# LED_PIPE_PROJECT.net
KiCad netlist of a schematic drawn in EAGLE
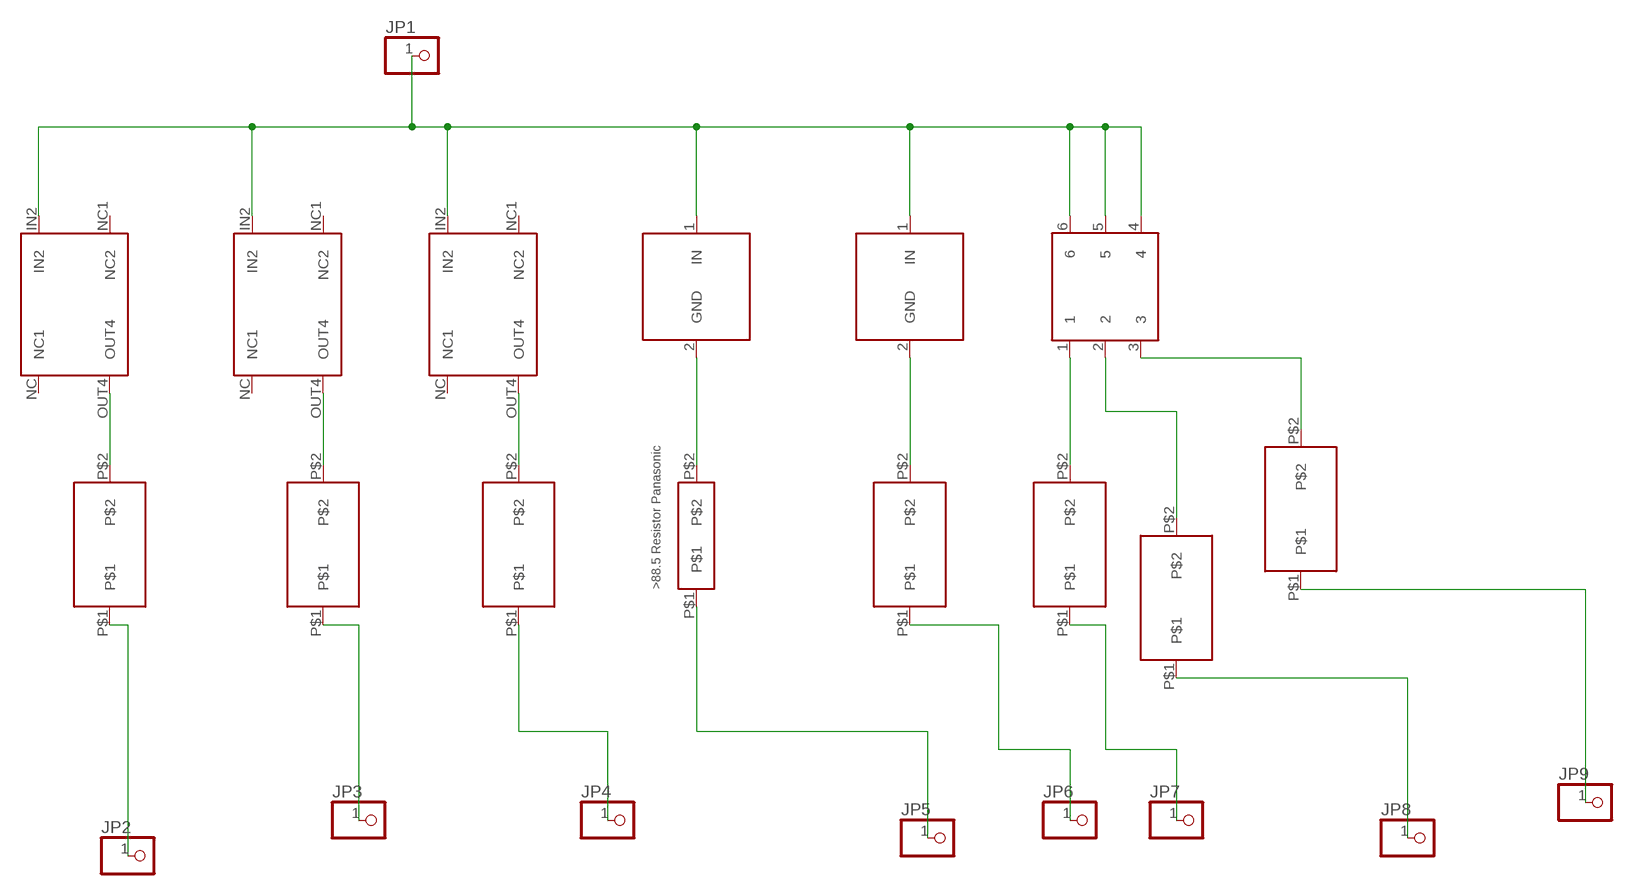
[diagram p0: schematic, sheet 1]

(export (version "E")
  (design (tool "Eeschema 10.0.6"))
  (components
    (comp (ref "JP1")
      (value "PINHD-1X1")
      (footprint "eagle-import:1X01")
      (libsource (lib "eagle-import") (part "PINHD-1X1"))
    )
    (comp (ref "JP2")
      (value "PINHD-1X1")
      (footprint "eagle-import:1X01")
      (libsource (lib "eagle-import") (part "PINHD-1X1"))
    )
    (comp (ref "JP3")
      (value "PINHD-1X1")
      (footprint "eagle-import:1X01")
      (libsource (lib "eagle-import") (part "PINHD-1X1"))
    )
    (comp (ref "JP4")
      (value "PINHD-1X1")
      (footprint "eagle-import:1X01")
      (libsource (lib "eagle-import") (part "PINHD-1X1"))
    )
    (comp (ref "JP5")
      (value "PINHD-1X1")
      (footprint "eagle-import:1X01")
      (libsource (lib "eagle-import") (part "PINHD-1X1"))
    )
    (comp (ref "JP6")
      (value "PINHD-1X1")
      (footprint "eagle-import:1X01")
      (libsource (lib "eagle-import") (part "PINHD-1X1"))
    )
    (comp (ref "JP7")
      (value "PINHD-1X1")
      (footprint "eagle-import:1X01")
      (libsource (lib "eagle-import") (part "PINHD-1X1"))
    )
    (comp (ref "JP8")
      (value "PINHD-1X1")
      (footprint "eagle-import:1X01")
      (libsource (lib "eagle-import") (part "PINHD-1X1"))
    )
    (comp (ref "JP9")
      (value "PINHD-1X1")
      (footprint "eagle-import:1X01")
      (libsource (lib "eagle-import") (part "PINHD-1X1"))
    )
    (comp (ref "U$1")
      (value "UV_LED")
      (footprint "eagle-import:UV_LED")
      (libsource (lib "eagle-import") (part "UV_LED"))
    )
    (comp (ref "U$2")
      (value "IR_LED")
      (footprint "eagle-import:IR_LED")
      (libsource (lib "eagle-import") (part "IR_LED"))
    )
    (comp (ref "U$3")
      (value "SMALL_RGB")
      (footprint "eagle-import:SMALL_RGB")
      (libsource (lib "eagle-import") (part "SMALL_RGB"))
    )
    (comp (ref "U$4")
      (value "SMALL_BRIGHT_COOL_WHITE")
      (footprint "eagle-import:SMALL_BRIGHT_COOL_WHITE")
      (libsource (lib "eagle-import") (part "SMALL_BRIGHT_COOL_WHITE"))
    )
    (comp (ref "U$5")
      (value "SMALL_BRIGHT_COOL_WHITE")
      (footprint "eagle-import:SMALL_BRIGHT_COOL_WHITE")
      (libsource (lib "eagle-import") (part "SMALL_BRIGHT_COOL_WHITE"))
    )
    (comp (ref "U$6")
      (value "SMALL_BRIGHT_COOL_WHITE")
      (footprint "eagle-import:SMALL_BRIGHT_COOL_WHITE")
      (libsource (lib "eagle-import") (part "SMALL_BRIGHT_COOL_WHITE"))
    )
    (comp (ref "U$7")
      (value "68_60_56_RESISTOR_VISHAY")
      (footprint "eagle-import:68_60_56_RESISTOR_VISHAY")
      (libsource (lib "eagle-import") (part "68_60_56_RESISTOR_VISHAY"))
    )
    (comp (ref "U$8")
      (value "68_60_56_RESISTOR_VISHAY")
      (footprint "eagle-import:68_60_56_RESISTOR_VISHAY")
      (libsource (lib "eagle-import") (part "68_60_56_RESISTOR_VISHAY"))
    )
    (comp (ref "U$9")
      (value "68_60_56_RESISTOR_VISHAY")
      (footprint "eagle-import:68_60_56_RESISTOR_VISHAY")
      (libsource (lib "eagle-import") (part "68_60_56_RESISTOR_VISHAY"))
    )
    (comp (ref "U$10")
      (value "88.5_RESISTOR_PANASONIC")
      (footprint "eagle-import:88.7_RESISTOR_PANASONIC")
      (libsource (lib "eagle-import") (part "88.5_RESISTOR_PANASONIC"))
    )
    (comp (ref "U$11")
      (value "68_60_56_RESISTOR_VISHAY")
      (footprint "eagle-import:68_60_56_RESISTOR_VISHAY")
      (libsource (lib "eagle-import") (part "68_60_56_RESISTOR_VISHAY"))
    )
    (comp (ref "U$12")
      (value "68_60_56_RESISTOR_VISHAY")
      (footprint "eagle-import:68_60_56_RESISTOR_VISHAY")
      (libsource (lib "eagle-import") (part "68_60_56_RESISTOR_VISHAY"))
    )
    (comp (ref "U$13")
      (value "68_60_56_RESISTOR_VISHAY")
      (footprint "eagle-import:68_60_56_RESISTOR_VISHAY")
      (libsource (lib "eagle-import") (part "68_60_56_RESISTOR_VISHAY"))
    )
    (comp (ref "U$14")
      (value "68_60_56_RESISTOR_VISHAY")
      (footprint "eagle-import:68_60_56_RESISTOR_VISHAY")
      (libsource (lib "eagle-import") (part "68_60_56_RESISTOR_VISHAY"))
    )
  )
  (nets
    (net (code "1") (name "Net-(JP2-Pad1)") (class "Default")
      (node (ref "JP2") (pin "1") (pinfunction "1_1") (pintype "passive"))
      (node (ref "U$7") (pin "P$1") (pinfunction "P$1_P$1") (pintype "bidirectional"))
    )
    (net (code "2") (name "Net-(JP3-Pad1)") (class "Default")
      (node (ref "JP3") (pin "1") (pinfunction "1_1") (pintype "passive"))
      (node (ref "U$8") (pin "P$1") (pinfunction "P$1_P$1") (pintype "bidirectional"))
    )
    (net (code "3") (name "Net-(JP4-Pad1)") (class "Default")
      (node (ref "JP4") (pin "1") (pinfunction "1_1") (pintype "passive"))
      (node (ref "U$9") (pin "P$1") (pinfunction "P$1_P$1") (pintype "bidirectional"))
    )
    (net (code "4") (name "Net-(JP5-Pad1)") (class "Default")
      (node (ref "JP5") (pin "1") (pinfunction "1_1") (pintype "passive"))
      (node (ref "U$10") (pin "P$1") (pinfunction "P$1_P$1") (pintype "bidirectional"))
    )
    (net (code "5") (name "Net-(JP6-Pad1)") (class "Default")
      (node (ref "JP6") (pin "1") (pinfunction "1_1") (pintype "passive"))
      (node (ref "U$11") (pin "P$1") (pinfunction "P$1_P$1") (pintype "bidirectional"))
    )
    (net (code "6") (name "Net-(JP7-Pad1)") (class "Default")
      (node (ref "JP7") (pin "1") (pinfunction "1_1") (pintype "passive"))
      (node (ref "U$12") (pin "P$1") (pinfunction "P$1_P$1") (pintype "bidirectional"))
    )
    (net (code "7") (name "Net-(JP8-Pad1)") (class "Default")
      (node (ref "JP8") (pin "1") (pinfunction "1_1") (pintype "passive"))
      (node (ref "U$13") (pin "P$1") (pinfunction "P$1_P$1") (pintype "bidirectional"))
    )
    (net (code "8") (name "Net-(JP9-Pad1)") (class "Default")
      (node (ref "JP9") (pin "1") (pinfunction "1_1") (pintype "passive"))
      (node (ref "U$14") (pin "P$1") (pinfunction "P$1_P$1") (pintype "bidirectional"))
    )
    (net (code "9") (name "Net-(U$1-GND)") (class "Default")
      (node (ref "U$1") (pin "2") (pinfunction "GND_2") (pintype "bidirectional"))
      (node (ref "U$10") (pin "P$2") (pinfunction "P$2_P$2") (pintype "bidirectional"))
    )
    (net (code "10") (name "Net-(U$1-IN)") (class "Default")
      (node (ref "JP1") (pin "1") (pinfunction "1_1") (pintype "passive"))
      (node (ref "U$1") (pin "1") (pinfunction "IN_1") (pintype "bidirectional"))
      (node (ref "U$2") (pin "1") (pinfunction "IN_1") (pintype "bidirectional"))
      (node (ref "U$3") (pin "4") (pinfunction "4_4") (pintype "bidirectional"))
      (node (ref "U$3") (pin "5") (pinfunction "5_5") (pintype "bidirectional"))
      (node (ref "U$3") (pin "6") (pinfunction "6_6") (pintype "bidirectional"))
      (node (ref "U$4") (pin "IN2") (pinfunction "IN2_IN2") (pintype "bidirectional"))
      (node (ref "U$5") (pin "IN2") (pinfunction "IN2_IN2") (pintype "bidirectional"))
      (node (ref "U$6") (pin "IN2") (pinfunction "IN2_IN2") (pintype "bidirectional"))
    )
    (net (code "11") (name "Net-(U$2-GND)") (class "Default")
      (node (ref "U$11") (pin "P$2") (pinfunction "P$2_P$2") (pintype "bidirectional"))
      (node (ref "U$2") (pin "2") (pinfunction "GND_2") (pintype "bidirectional"))
    )
    (net (code "12") (name "Net-(U$4-PadOUT4)") (class "Default")
      (node (ref "U$4") (pin "OUT4") (pinfunction "OUT4_OUT4") (pintype "bidirectional"))
      (node (ref "U$9") (pin "P$2") (pinfunction "P$2_P$2") (pintype "bidirectional"))
    )
    (net (code "13") (name "Net-(U$5-PadOUT4)") (class "Default")
      (node (ref "U$5") (pin "OUT4") (pinfunction "OUT4_OUT4") (pintype "bidirectional"))
      (node (ref "U$8") (pin "P$2") (pinfunction "P$2_P$2") (pintype "bidirectional"))
    )
    (net (code "14") (name "Net-(U$6-PadOUT4)") (class "Default")
      (node (ref "U$6") (pin "OUT4") (pinfunction "OUT4_OUT4") (pintype "bidirectional"))
      (node (ref "U$7") (pin "P$2") (pinfunction "P$2_P$2") (pintype "bidirectional"))
    )
    (net (code "15") (name "Net-(U$12-PadP$2)") (class "Default")
      (node (ref "U$12") (pin "P$2") (pinfunction "P$2_P$2") (pintype "bidirectional"))
      (node (ref "U$3") (pin "1") (pinfunction "1_1") (pintype "bidirectional"))
    )
    (net (code "16") (name "Net-(U$13-PadP$2)") (class "Default")
      (node (ref "U$13") (pin "P$2") (pinfunction "P$2_P$2") (pintype "bidirectional"))
      (node (ref "U$3") (pin "2") (pinfunction "2_2") (pintype "bidirectional"))
    )
    (net (code "17") (name "Net-(U$14-PadP$2)") (class "Default")
      (node (ref "U$14") (pin "P$2") (pinfunction "P$2_P$2") (pintype "bidirectional"))
      (node (ref "U$3") (pin "3") (pinfunction "3_3") (pintype "bidirectional"))
    )
    (net (code "18") (name "unconnected-(U$4-NC1-PadNC)") (class "Default")
      (node (ref "U$4") (pin "NC") (pinfunction "NC1_NC") (pintype "bidirectional"))
    )
    (net (code "19") (name "unconnected-(U$4-NC2-PadNC1)") (class "Default")
      (node (ref "U$4") (pin "NC1") (pinfunction "NC2_NC1") (pintype "bidirectional"))
    )
    (net (code "20") (name "unconnected-(U$5-NC1-PadNC)") (class "Default")
      (node (ref "U$5") (pin "NC") (pinfunction "NC1_NC") (pintype "bidirectional"))
    )
    (net (code "21") (name "unconnected-(U$5-NC2-PadNC1)") (class "Default")
      (node (ref "U$5") (pin "NC1") (pinfunction "NC2_NC1") (pintype "bidirectional"))
    )
    (net (code "22") (name "unconnected-(U$6-NC1-PadNC)") (class "Default")
      (node (ref "U$6") (pin "NC") (pinfunction "NC1_NC") (pintype "bidirectional"))
    )
    (net (code "23") (name "unconnected-(U$6-NC2-PadNC1)") (class "Default")
      (node (ref "U$6") (pin "NC1") (pinfunction "NC2_NC1") (pintype "bidirectional"))
    )
  )
)
